# Sheet1.net
KiCad netlist of a schematic drawn in Altium Designer
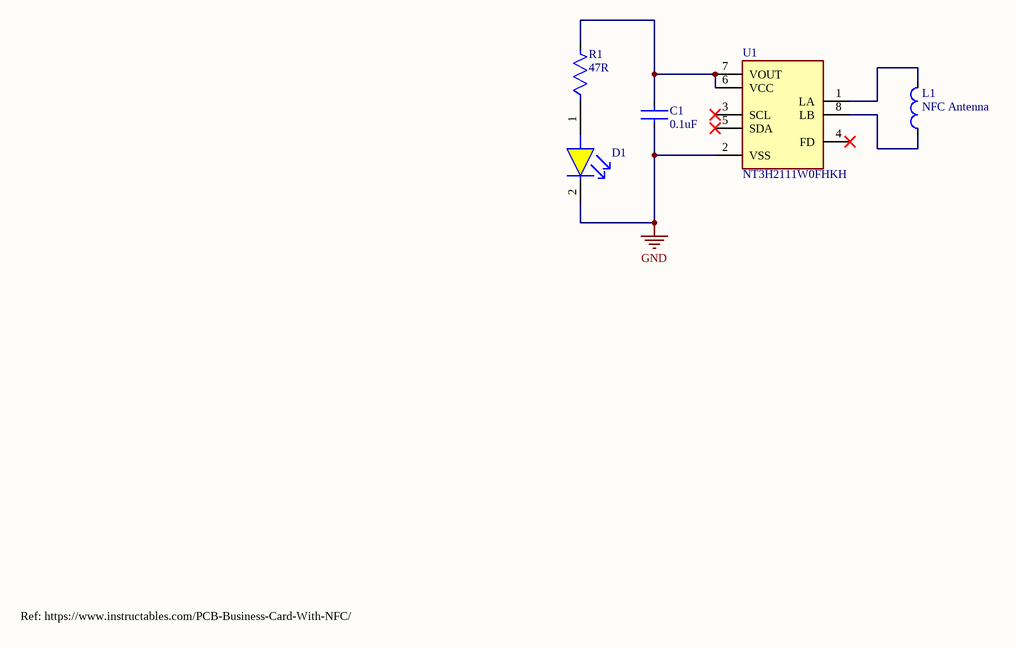
[diagram p0: Sheet1.SchDoc]

(export (version "E")
  (design (tool "Eeschema 10.0.6"))
  (components
    (comp (ref "C1")
      (value "0.1uF")
      (footprint "C_0603")
      (description "Ceramic Capacitor 0.1uF 10% X7R 50V 0603 T/R")
      (fields
        (field (name "MANUFACTURER") "Samsung")
        (field (name "MANUFACTURER PART NUMBER") "CL10B104KB8WPND")
      )
      (libsource (lib "OP_Library") (part "Cap 0.1uF 50V 10% X7R 0603"))
    )
    (comp (ref "D1")
      (value "Yellow")
      (footprint "LED_0603")
      (description "APT1608SYCK Yellow LED; 590 nm 1608 (0603) Clear; Rectangle Lens SMD package")
      (fields
        (field (name "MANUFACTURER") "Kingbright")
        (field (name "MANUFACTURER PART NUMBER") "APT1608SYCK")
      )
      (libsource (lib "OP_Library") (part "LED Yellow 2V 20mA 0603"))
    )
    (comp (ref "L1")
      (value "NFC Antenna")
      (footprint "25X48MM_NFC_ANTENNA")
      (description "Antenna for NFC")
      (libsource (lib "OP_Library") (part "Antenna NFC 25X48MM"))
    )
    (comp (ref "R1")
      (value "47R")
      (footprint "R_0603")
      (fields
        (field (name "MANUFACTURER") "Yageo")
        (field (name "MANUFACTURER PART NUMBER") "RC0603FR-7W47RL")
        (field (name "TOLERANCE") "1%")
      )
      (libsource (lib "OP_Library") (part "Res 47R 1% 1/5W 0603"))
    )
    (comp (ref "U1")
      (value "NT3H2111W0FHKH")
      (footprint "XFQFN-8")
      (description "NFC/RFID Tag and Transponder IC 13560kHz 1KByte Automotive 8-Pin XQFN EP T/R")
      (fields (field (name "MANUFACTURER") "NXP Semiconductors"))
      (libsource (lib "OP_Library") (part "IC RFID Transponder 13.56MHz XQFN-8"))
    )
  )
  (nets
    (net (code "1") (name "GND") (class "Default")
      (node (ref "C1") (pin "1") (pinfunction "1_1") (pintype "passive"))
      (node (ref "D1") (pin "2") (pinfunction "Green_C_2") (pintype "passive"))
      (node (ref "U1") (pin "2") (pinfunction "VSS_2") (pintype "passive"))
    )
    (net (code "2") (name "Net-(D1-Red_A)") (class "Default")
      (node (ref "D1") (pin "1") (pinfunction "Red_A_1") (pintype "passive"))
      (node (ref "R1") (pin "1") (pinfunction "1_1") (pintype "passive"))
    )
    (net (code "3") (name "Net-(U1-LA)") (class "Default")
      (node (ref "L1") (pin "2") (pinfunction "2_2") (pintype "passive"))
      (node (ref "U1") (pin "1") (pinfunction "LA_1") (pintype "passive"))
    )
    (net (code "4") (name "Net-(U1-LB)") (class "Default")
      (node (ref "L1") (pin "1") (pinfunction "1_1") (pintype "passive"))
      (node (ref "U1") (pin "8") (pinfunction "LB_8") (pintype "passive"))
    )
    (net (code "5") (name "Net-(U1-VCC)") (class "Default")
      (node (ref "C1") (pin "2") (pinfunction "2_2") (pintype "passive"))
      (node (ref "R1") (pin "2") (pinfunction "2_2") (pintype "passive"))
      (node (ref "U1") (pin "6") (pinfunction "VCC_6") (pintype "passive"))
      (node (ref "U1") (pin "7") (pinfunction "VOUT_7") (pintype "passive"))
    )
    (net (code "6") (name "unconnected-(U1-FD-Pad4)") (class "Default")
      (node (ref "U1") (pin "4") (pinfunction "FD_4") (pintype "passive+no_connect"))
    )
    (net (code "7") (name "unconnected-(U1-SCL-Pad3)") (class "Default")
      (node (ref "U1") (pin "3") (pinfunction "SCL_3") (pintype "passive+no_connect"))
    )
    (net (code "8") (name "unconnected-(U1-SDA-Pad5)") (class "Default")
      (node (ref "U1") (pin "5") (pinfunction "SDA_5") (pintype "passive+no_connect"))
    )
  )
)
